# board_vending.net
KiCad netlist of a schematic drawn in EAGLE
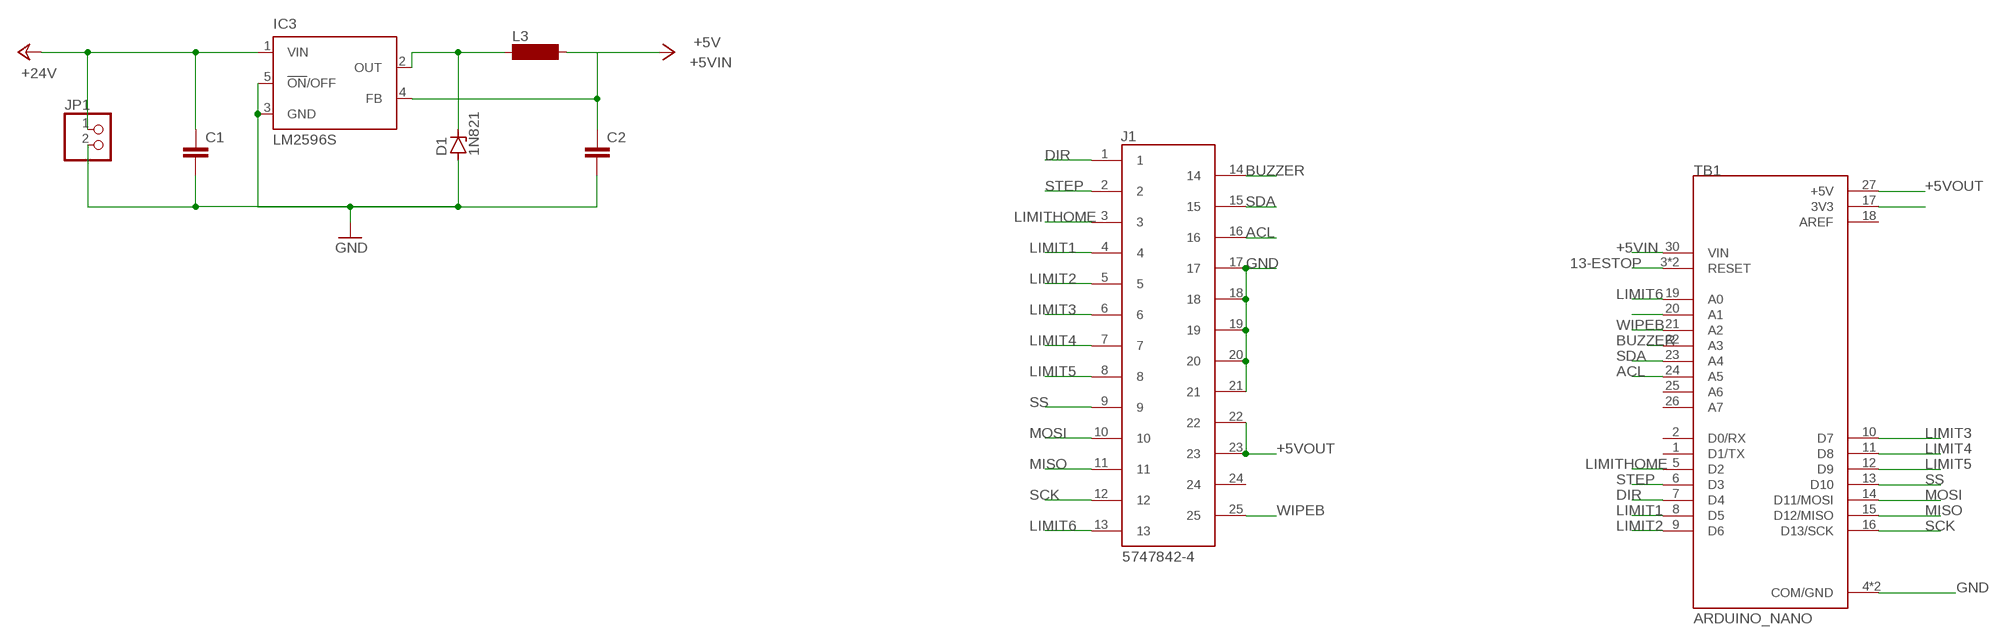
[diagram p0: schematic, sheet 1]

(export (version "E")
  (design (tool "Eeschema 10.0.6"))
  (components
    (comp (ref "C1")
      (value "C5/7.2")
      (footprint "eagle-import:C5B7.2")
      (libsource (lib "eagle-import") (part "C5/7.2"))
    )
    (comp (ref "C2")
      (value "C5/7.2")
      (footprint "eagle-import:C5B7.2")
      (libsource (lib "eagle-import") (part "C5/7.2"))
    )
    (comp (ref "D1")
      (value "1N821")
      (footprint "eagle-import:DO35Z10")
      (libsource (lib "eagle-import") (part "1N821"))
    )
    (comp (ref "IC3")
      (value "LM2596S")
      (footprint "eagle-import:TO263-5")
      (fields (field (name "MF") "NATIONAL SEMICONDUCTOR") (field (name "MPN") "LM2596S-ADJ/NOPB"))
      (libsource (lib "eagle-import") (part "LM2596S"))
    )
    (comp (ref "J1")
      (value "5747842-4")
      (footprint "eagle-import:TE_5747842-4")
      (fields (field (name "MF") "TE Connectivity"))
      (libsource (lib "eagle-import") (part "5747842-4"))
    )
    (comp (ref "JP1")
      (value "PINHD-1X2")
      (footprint "eagle-import:1X02")
      (libsource (lib "eagle-import") (part "PINHD-1X2"))
    )
    (comp (ref "L3")
      (value "BS75")
      (footprint "eagle-import:BS75")
      (libsource (lib "eagle-import") (part "BS75"))
    )
    (comp (ref "TB1")
      (value "ARDUINO_NANO")
      (footprint "eagle-import:SHIELD_ARDUINO_NANO")
      (fields (field (name "MF") "Arduino") (field (name "MP") "Arduino Nano"))
      (libsource (lib "eagle-import") (part "ARDUINO_NANO"))
    )
  )
  (nets
    (net (code "1") (name "+5V") (class "Default")
      (node (ref "C2") (pin "1") (pinfunction "1_1") (pintype "passive"))
      (node (ref "IC3") (pin "4") (pinfunction "FB_4") (pintype "input"))
      (node (ref "L3") (pin "2") (pinfunction "2_2") (pintype "passive"))
      (node (ref "TB1") (pin "30") (pinfunction "VIN_30") (pintype "input"))
    )
    (net (code "2") (name "+24V") (class "Default")
      (node (ref "C1") (pin "1") (pinfunction "1_1") (pintype "passive"))
      (node (ref "IC3") (pin "1") (pinfunction "VIN_1") (pintype "input"))
      (node (ref "JP1") (pin "1") (pinfunction "1_1") (pintype "passive"))
    )
    (net (code "3") (name "/+5VOUT") (class "Default")
      (node (ref "J1") (pin "22") (pinfunction "22_22") (pintype "passive"))
      (node (ref "J1") (pin "23") (pinfunction "23_23") (pintype "passive"))
      (node (ref "TB1") (pin "27") (pinfunction "+5V_27") (pintype "power_in"))
    )
    (net (code "4") (name "/13-ESTOP") (class "Default")
      (node (ref "TB1") (pin "28") (pinfunction "RESET_28") (pintype "input"))
      (node (ref "TB1") (pin "3") (pinfunction "RESET_3") (pintype "input"))
    )
    (net (code "5") (name "/ACL") (class "Default")
      (node (ref "J1") (pin "16") (pinfunction "16_16") (pintype "passive"))
      (node (ref "TB1") (pin "24") (pinfunction "A5_24") (pintype "input"))
    )
    (net (code "6") (name "/AREF") (class "Default")
      (node (ref "TB1") (pin "18") (pinfunction "AREF_18") (pintype "power_in"))
    )
    (net (code "7") (name "/BUZZER") (class "Default")
      (node (ref "J1") (pin "14") (pinfunction "14_14") (pintype "passive"))
      (node (ref "TB1") (pin "22") (pinfunction "A3_22") (pintype "input"))
    )
    (net (code "8") (name "/DIR") (class "Default")
      (node (ref "J1") (pin "1") (pinfunction "1_1") (pintype "passive"))
      (node (ref "TB1") (pin "7") (pinfunction "D4_7") (pintype "bidirectional"))
    )
    (net (code "9") (name "/LIMIT1") (class "Default")
      (node (ref "J1") (pin "4") (pinfunction "4_4") (pintype "passive"))
      (node (ref "TB1") (pin "8") (pinfunction "D5_8") (pintype "bidirectional"))
    )
    (net (code "10") (name "/LIMIT2") (class "Default")
      (node (ref "J1") (pin "5") (pinfunction "5_5") (pintype "passive"))
      (node (ref "TB1") (pin "9") (pinfunction "D6_9") (pintype "bidirectional"))
    )
    (net (code "11") (name "/LIMIT3") (class "Default")
      (node (ref "J1") (pin "6") (pinfunction "6_6") (pintype "passive"))
      (node (ref "TB1") (pin "10") (pinfunction "D7_10") (pintype "bidirectional"))
    )
    (net (code "12") (name "/LIMIT4") (class "Default")
      (node (ref "J1") (pin "7") (pinfunction "7_7") (pintype "passive"))
      (node (ref "TB1") (pin "11") (pinfunction "D8_11") (pintype "bidirectional"))
    )
    (net (code "13") (name "/LIMIT5") (class "Default")
      (node (ref "J1") (pin "8") (pinfunction "8_8") (pintype "passive"))
      (node (ref "TB1") (pin "12") (pinfunction "D9_12") (pintype "bidirectional"))
    )
    (net (code "14") (name "/LIMIT6") (class "Default")
      (node (ref "J1") (pin "13") (pinfunction "13_13") (pintype "passive"))
      (node (ref "TB1") (pin "19") (pinfunction "A0_19") (pintype "input"))
    )
    (net (code "15") (name "/LIMITHOME") (class "Default")
      (node (ref "J1") (pin "3") (pinfunction "3_3") (pintype "passive"))
      (node (ref "TB1") (pin "5") (pinfunction "D2_5") (pintype "bidirectional"))
    )
    (net (code "16") (name "/MISO") (class "Default")
      (node (ref "J1") (pin "11") (pinfunction "11_11") (pintype "passive"))
      (node (ref "TB1") (pin "15") (pinfunction "D12/MISO_15") (pintype "bidirectional"))
    )
    (net (code "17") (name "/MOSI") (class "Default")
      (node (ref "J1") (pin "10") (pinfunction "10_10") (pintype "passive"))
      (node (ref "TB1") (pin "14") (pinfunction "D11/MOSI_14") (pintype "bidirectional"))
    )
    (net (code "18") (name "/SCK") (class "Default")
      (node (ref "J1") (pin "12") (pinfunction "12_12") (pintype "passive"))
      (node (ref "TB1") (pin "16") (pinfunction "D13/SCK_16") (pintype "bidirectional"))
    )
    (net (code "19") (name "/SDA") (class "Default")
      (node (ref "J1") (pin "15") (pinfunction "15_15") (pintype "passive"))
      (node (ref "TB1") (pin "23") (pinfunction "A4_23") (pintype "input"))
    )
    (net (code "20") (name "/SS") (class "Default")
      (node (ref "J1") (pin "9") (pinfunction "9_9") (pintype "passive"))
      (node (ref "TB1") (pin "13") (pinfunction "D10_13") (pintype "bidirectional"))
    )
    (net (code "21") (name "/STEP") (class "Default")
      (node (ref "J1") (pin "2") (pinfunction "2_2") (pintype "passive"))
      (node (ref "TB1") (pin "6") (pinfunction "D3_6") (pintype "bidirectional"))
    )
    (net (code "22") (name "/WIPEB") (class "Default")
      (node (ref "J1") (pin "25") (pinfunction "25_25") (pintype "passive"))
      (node (ref "TB1") (pin "21") (pinfunction "A2_21") (pintype "input"))
    )
    (net (code "23") (name "GND") (class "Default")
      (node (ref "C1") (pin "2") (pinfunction "2_2") (pintype "passive"))
      (node (ref "C2") (pin "2") (pinfunction "2_2") (pintype "passive"))
      (node (ref "D1") (pin "A") (pinfunction "A_A") (pintype "passive"))
      (node (ref "IC3") (pin "3") (pinfunction "GND_3") (pintype "power_in"))
      (node (ref "IC3") (pin "5") (pinfunction "~{ON}/OFF_5") (pintype "input"))
      (node (ref "J1") (pin "17") (pinfunction "17_17") (pintype "passive"))
      (node (ref "J1") (pin "18") (pinfunction "18_18") (pintype "passive"))
      (node (ref "J1") (pin "19") (pinfunction "19_19") (pintype "passive"))
      (node (ref "J1") (pin "20") (pinfunction "20_20") (pintype "passive"))
      (node (ref "J1") (pin "21") (pinfunction "21_21") (pintype "passive"))
      (node (ref "JP1") (pin "2") (pinfunction "2_2") (pintype "passive"))
      (node (ref "TB1") (pin "29") (pinfunction "COM/GND_29") (pintype "power_in"))
      (node (ref "TB1") (pin "4") (pinfunction "COM/GND_4") (pintype "power_in"))
    )
    (net (code "24") (name "Net-(IC3-OUT)") (class "Default")
      (node (ref "D1") (pin "C") (pinfunction "C_C") (pintype "passive"))
      (node (ref "IC3") (pin "2") (pinfunction "OUT_2") (pintype "output"))
      (node (ref "L3") (pin "1") (pinfunction "1_1") (pintype "passive"))
    )
    (net (code "25") (name "unconnected-(J1-Pad24)") (class "Default")
      (node (ref "J1") (pin "24") (pinfunction "24_24") (pintype "passive"))
    )
    (net (code "26") (name "unconnected-(TB1-3V3-Pad17)") (class "Default")
      (node (ref "TB1") (pin "17") (pinfunction "3V3_17") (pintype "power_in"))
    )
    (net (code "27") (name "unconnected-(TB1-A1-Pad20)") (class "Default")
      (node (ref "TB1") (pin "20") (pinfunction "A1_20") (pintype "input"))
    )
    (net (code "28") (name "unconnected-(TB1-A6-Pad25)") (class "Default")
      (node (ref "TB1") (pin "25") (pinfunction "A6_25") (pintype "input"))
    )
    (net (code "29") (name "unconnected-(TB1-A7-Pad26)") (class "Default")
      (node (ref "TB1") (pin "26") (pinfunction "A7_26") (pintype "input"))
    )
    (net (code "30") (name "unconnected-(TB1-D0{slash}RX-Pad2)") (class "Default")
      (node (ref "TB1") (pin "2") (pinfunction "D0/RX_2") (pintype "bidirectional"))
    )
    (net (code "31") (name "unconnected-(TB1-D1{slash}TX-Pad1)") (class "Default")
      (node (ref "TB1") (pin "1") (pinfunction "D1/TX_1") (pintype "bidirectional"))
    )
  )
)
